# Eurorack_passive_dist.net
KiCad netlist of a schematic drawn in EAGLE
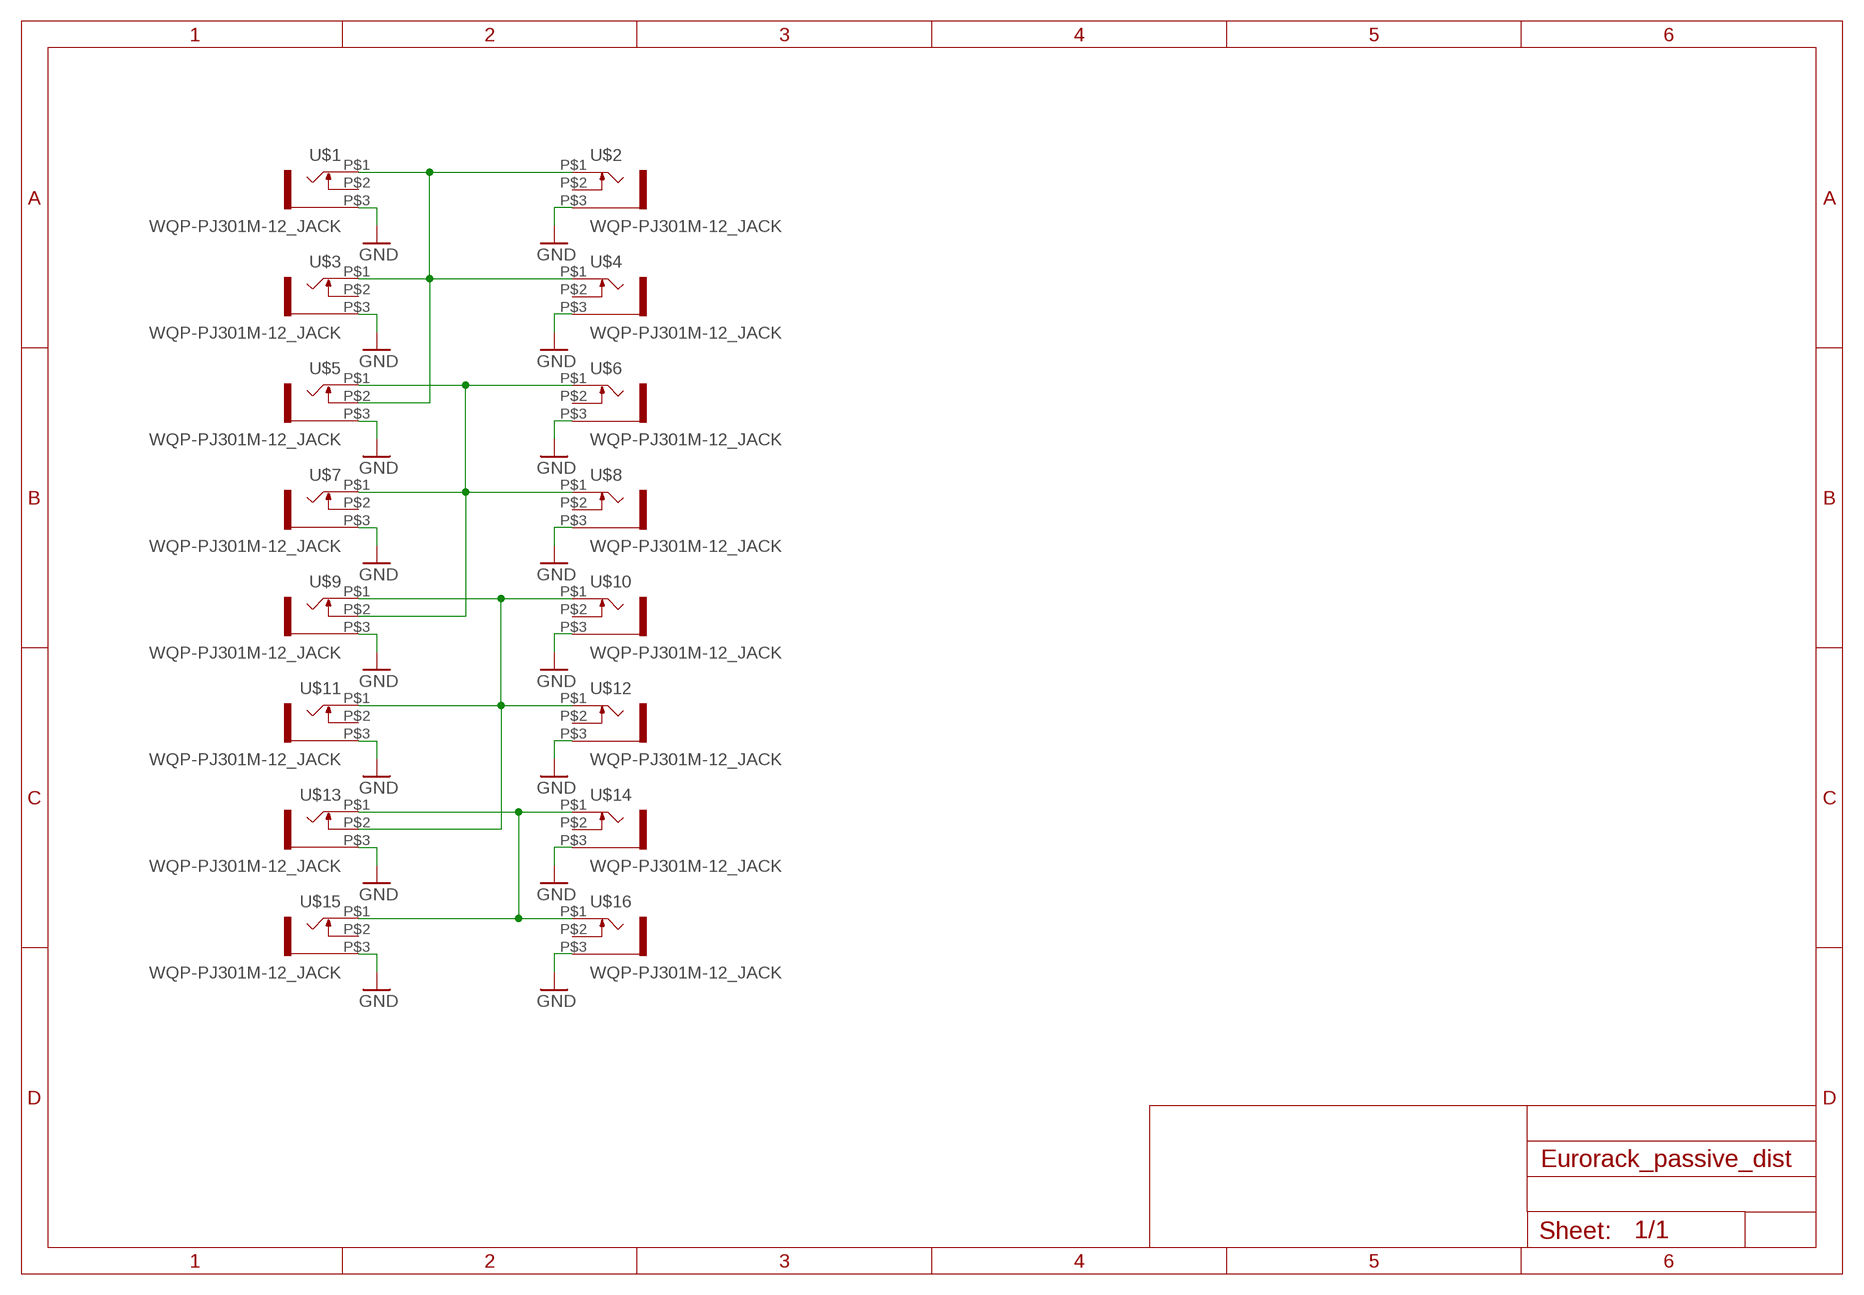
[diagram p0: schematic, sheet 1]

(export (version "E")
  (design (tool "Eeschema 10.0.6"))
  (components
    (comp (ref "U$1")
      (value "WQP-PJ301M-12_JACK")
      (footprint "eagle-import:WQP-PJ301M-12_JACK")
      (libsource (lib "eagle-import") (part "WQP-PJ301M-12_JACK"))
    )
    (comp (ref "U$2")
      (value "WQP-PJ301M-12_JACK")
      (footprint "eagle-import:WQP-PJ301M-12_JACK")
      (libsource (lib "eagle-import") (part "WQP-PJ301M-12_JACK"))
    )
    (comp (ref "U$3")
      (value "WQP-PJ301M-12_JACK")
      (footprint "eagle-import:WQP-PJ301M-12_JACK")
      (libsource (lib "eagle-import") (part "WQP-PJ301M-12_JACK"))
    )
    (comp (ref "U$4")
      (value "WQP-PJ301M-12_JACK")
      (footprint "eagle-import:WQP-PJ301M-12_JACK")
      (libsource (lib "eagle-import") (part "WQP-PJ301M-12_JACK"))
    )
    (comp (ref "U$5")
      (value "WQP-PJ301M-12_JACK")
      (footprint "eagle-import:WQP-PJ301M-12_JACK")
      (libsource (lib "eagle-import") (part "WQP-PJ301M-12_JACK"))
    )
    (comp (ref "U$6")
      (value "WQP-PJ301M-12_JACK")
      (footprint "eagle-import:WQP-PJ301M-12_JACK")
      (libsource (lib "eagle-import") (part "WQP-PJ301M-12_JACK"))
    )
    (comp (ref "U$7")
      (value "WQP-PJ301M-12_JACK")
      (footprint "eagle-import:WQP-PJ301M-12_JACK")
      (libsource (lib "eagle-import") (part "WQP-PJ301M-12_JACK"))
    )
    (comp (ref "U$8")
      (value "WQP-PJ301M-12_JACK")
      (footprint "eagle-import:WQP-PJ301M-12_JACK")
      (libsource (lib "eagle-import") (part "WQP-PJ301M-12_JACK"))
    )
    (comp (ref "U$9")
      (value "WQP-PJ301M-12_JACK")
      (footprint "eagle-import:WQP-PJ301M-12_JACK")
      (libsource (lib "eagle-import") (part "WQP-PJ301M-12_JACK"))
    )
    (comp (ref "U$10")
      (value "WQP-PJ301M-12_JACK")
      (footprint "eagle-import:WQP-PJ301M-12_JACK")
      (libsource (lib "eagle-import") (part "WQP-PJ301M-12_JACK"))
    )
    (comp (ref "U$11")
      (value "WQP-PJ301M-12_JACK")
      (footprint "eagle-import:WQP-PJ301M-12_JACK")
      (libsource (lib "eagle-import") (part "WQP-PJ301M-12_JACK"))
    )
    (comp (ref "U$12")
      (value "WQP-PJ301M-12_JACK")
      (footprint "eagle-import:WQP-PJ301M-12_JACK")
      (libsource (lib "eagle-import") (part "WQP-PJ301M-12_JACK"))
    )
    (comp (ref "U$13")
      (value "WQP-PJ301M-12_JACK")
      (footprint "eagle-import:WQP-PJ301M-12_JACK")
      (libsource (lib "eagle-import") (part "WQP-PJ301M-12_JACK"))
    )
    (comp (ref "U$14")
      (value "WQP-PJ301M-12_JACK")
      (footprint "eagle-import:WQP-PJ301M-12_JACK")
      (libsource (lib "eagle-import") (part "WQP-PJ301M-12_JACK"))
    )
    (comp (ref "U$15")
      (value "WQP-PJ301M-12_JACK")
      (footprint "eagle-import:WQP-PJ301M-12_JACK")
      (libsource (lib "eagle-import") (part "WQP-PJ301M-12_JACK"))
    )
    (comp (ref "U$16")
      (value "WQP-PJ301M-12_JACK")
      (footprint "eagle-import:WQP-PJ301M-12_JACK")
      (libsource (lib "eagle-import") (part "WQP-PJ301M-12_JACK"))
    )
  )
  (nets
    (net (code "1") (name "GND") (class "Default")
      (node (ref "U$1") (pin "P$3") (pinfunction "1_P$3") (pintype "passive"))
      (node (ref "U$10") (pin "P$3") (pinfunction "1_P$3") (pintype "passive"))
      (node (ref "U$11") (pin "P$3") (pinfunction "1_P$3") (pintype "passive"))
      (node (ref "U$12") (pin "P$3") (pinfunction "1_P$3") (pintype "passive"))
      (node (ref "U$13") (pin "P$3") (pinfunction "1_P$3") (pintype "passive"))
      (node (ref "U$14") (pin "P$3") (pinfunction "1_P$3") (pintype "passive"))
      (node (ref "U$15") (pin "P$3") (pinfunction "1_P$3") (pintype "passive"))
      (node (ref "U$16") (pin "P$3") (pinfunction "1_P$3") (pintype "passive"))
      (node (ref "U$2") (pin "P$3") (pinfunction "1_P$3") (pintype "passive"))
      (node (ref "U$3") (pin "P$3") (pinfunction "1_P$3") (pintype "passive"))
      (node (ref "U$4") (pin "P$3") (pinfunction "1_P$3") (pintype "passive"))
      (node (ref "U$5") (pin "P$3") (pinfunction "1_P$3") (pintype "passive"))
      (node (ref "U$6") (pin "P$3") (pinfunction "1_P$3") (pintype "passive"))
      (node (ref "U$7") (pin "P$3") (pinfunction "1_P$3") (pintype "passive"))
      (node (ref "U$8") (pin "P$3") (pinfunction "1_P$3") (pintype "passive"))
      (node (ref "U$9") (pin "P$3") (pinfunction "1_P$3") (pintype "passive"))
    )
    (net (code "2") (name "Net-(U$1-2)") (class "Default")
      (node (ref "U$1") (pin "P$1") (pinfunction "2_P$1") (pintype "passive"))
      (node (ref "U$2") (pin "P$1") (pinfunction "2_P$1") (pintype "passive"))
      (node (ref "U$3") (pin "P$1") (pinfunction "2_P$1") (pintype "passive"))
      (node (ref "U$4") (pin "P$1") (pinfunction "2_P$1") (pintype "passive"))
      (node (ref "U$5") (pin "P$2") (pinfunction "3_P$2") (pintype "passive"))
    )
    (net (code "3") (name "Net-(U$5-2)") (class "Default")
      (node (ref "U$5") (pin "P$1") (pinfunction "2_P$1") (pintype "passive"))
      (node (ref "U$6") (pin "P$1") (pinfunction "2_P$1") (pintype "passive"))
      (node (ref "U$7") (pin "P$1") (pinfunction "2_P$1") (pintype "passive"))
      (node (ref "U$8") (pin "P$1") (pinfunction "2_P$1") (pintype "passive"))
      (node (ref "U$9") (pin "P$2") (pinfunction "3_P$2") (pintype "passive"))
    )
    (net (code "4") (name "Net-(U$10-2)") (class "Default")
      (node (ref "U$10") (pin "P$1") (pinfunction "2_P$1") (pintype "passive"))
      (node (ref "U$11") (pin "P$1") (pinfunction "2_P$1") (pintype "passive"))
      (node (ref "U$12") (pin "P$1") (pinfunction "2_P$1") (pintype "passive"))
      (node (ref "U$13") (pin "P$2") (pinfunction "3_P$2") (pintype "passive"))
      (node (ref "U$9") (pin "P$1") (pinfunction "2_P$1") (pintype "passive"))
    )
    (net (code "5") (name "Net-(U$13-2)") (class "Default")
      (node (ref "U$13") (pin "P$1") (pinfunction "2_P$1") (pintype "passive"))
      (node (ref "U$14") (pin "P$1") (pinfunction "2_P$1") (pintype "passive"))
      (node (ref "U$15") (pin "P$1") (pinfunction "2_P$1") (pintype "passive"))
      (node (ref "U$16") (pin "P$1") (pinfunction "2_P$1") (pintype "passive"))
    )
    (net (code "6") (name "unconnected-(U$1-3-PadP$2)") (class "Default")
      (node (ref "U$1") (pin "P$2") (pinfunction "3_P$2") (pintype "passive"))
    )
    (net (code "7") (name "unconnected-(U$2-3-PadP$2)") (class "Default")
      (node (ref "U$2") (pin "P$2") (pinfunction "3_P$2") (pintype "passive"))
    )
    (net (code "8") (name "unconnected-(U$3-3-PadP$2)") (class "Default")
      (node (ref "U$3") (pin "P$2") (pinfunction "3_P$2") (pintype "passive"))
    )
    (net (code "9") (name "unconnected-(U$4-3-PadP$2)") (class "Default")
      (node (ref "U$4") (pin "P$2") (pinfunction "3_P$2") (pintype "passive"))
    )
    (net (code "10") (name "unconnected-(U$6-3-PadP$2)") (class "Default")
      (node (ref "U$6") (pin "P$2") (pinfunction "3_P$2") (pintype "passive"))
    )
    (net (code "11") (name "unconnected-(U$7-3-PadP$2)") (class "Default")
      (node (ref "U$7") (pin "P$2") (pinfunction "3_P$2") (pintype "passive"))
    )
    (net (code "12") (name "unconnected-(U$8-3-PadP$2)") (class "Default")
      (node (ref "U$8") (pin "P$2") (pinfunction "3_P$2") (pintype "passive"))
    )
    (net (code "13") (name "unconnected-(U$10-3-PadP$2)") (class "Default")
      (node (ref "U$10") (pin "P$2") (pinfunction "3_P$2") (pintype "passive"))
    )
    (net (code "14") (name "unconnected-(U$11-3-PadP$2)") (class "Default")
      (node (ref "U$11") (pin "P$2") (pinfunction "3_P$2") (pintype "passive"))
    )
    (net (code "15") (name "unconnected-(U$12-3-PadP$2)") (class "Default")
      (node (ref "U$12") (pin "P$2") (pinfunction "3_P$2") (pintype "passive"))
    )
    (net (code "16") (name "unconnected-(U$14-3-PadP$2)") (class "Default")
      (node (ref "U$14") (pin "P$2") (pinfunction "3_P$2") (pintype "passive"))
    )
    (net (code "17") (name "unconnected-(U$15-3-PadP$2)") (class "Default")
      (node (ref "U$15") (pin "P$2") (pinfunction "3_P$2") (pintype "passive"))
    )
    (net (code "18") (name "unconnected-(U$16-3-PadP$2)") (class "Default")
      (node (ref "U$16") (pin "P$2") (pinfunction "3_P$2") (pintype "passive"))
    )
  )
)
